# output3.net
KiCad netlist of a schematic drawn in Altium Designer
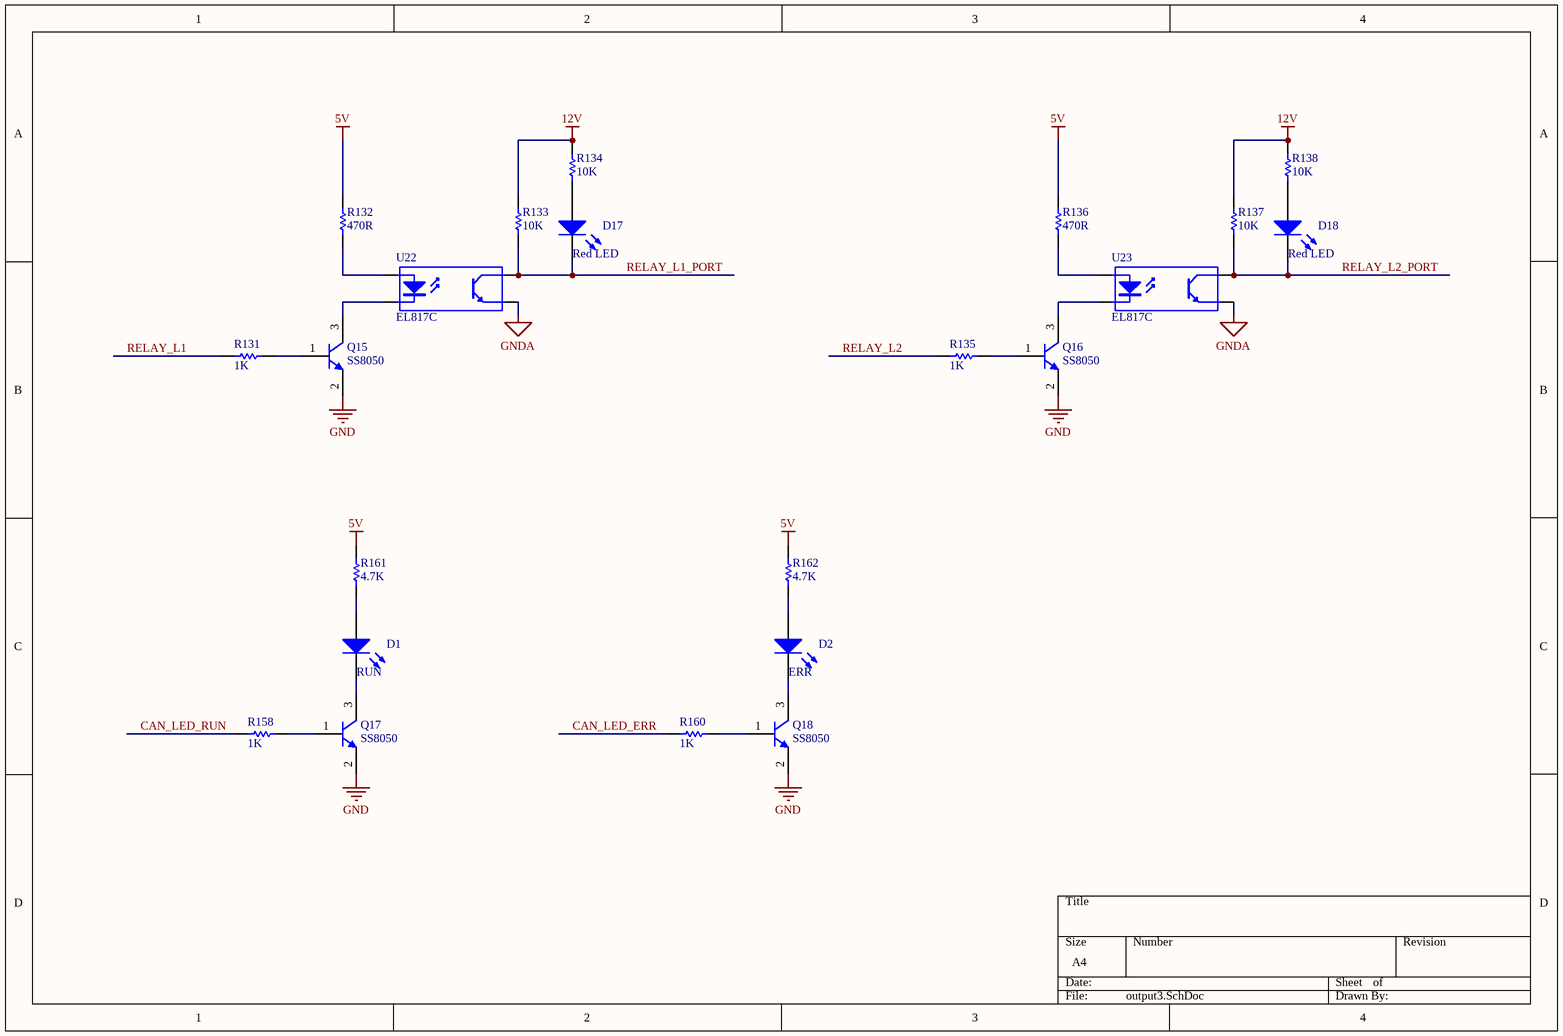
[diagram p0: output3.SchDoc]

(export (version "E")
  (design (tool "Eeschema 10.0.6"))
  (components
    (comp (ref "D1")
      (value "RUN")
      (footprint "CD2012-0805")
      (description "Green LED,Can bus indicator for run status.")
      (fields (field (name "PUBLISHER") "Altium Limited"))
      (libsource (lib "Miscellaneous Devices") (part "LED1"))
    )
    (comp (ref "D2")
      (value "ERR")
      (footprint "CD2012-0805")
      (description "Red LED,Can bus indicator for err status.")
      (fields (field (name "PUBLISHER") "Altium Limited"))
      (libsource (lib "Miscellaneous Devices") (part "LED1"))
    )
    (comp (ref "D17")
      (value "Red LED")
      (footprint "LED254A")
      (description "Red LED ,SIP, Dia =3mm")
      (fields (field (name "PUBLISHER") "Altium Limited"))
      (libsource (lib "Miscellaneous Devices") (part "LED1"))
    )
    (comp (ref "D18")
      (value "Red LED")
      (footprint "LED254A")
      (description "Red LED ,SIP, Dia =3mm")
      (fields (field (name "PUBLISHER") "Altium Limited"))
      (libsource (lib "Miscellaneous Devices") (part "LED1"))
    )
    (comp (ref "Q15")
      (value "SS8050")
      (footprint "SOT-23_N")
      (description "NPN BISS Transistor")
      (fields (field (name "PUBLISHER") "Altium Limited"))
      (libsource (lib "Philips Discrete BJT - Low Power") (part "PMMT491A"))
    )
    (comp (ref "Q16")
      (value "SS8050")
      (footprint "SOT-23_N")
      (description "NPN BISS Transistor")
      (fields (field (name "PUBLISHER") "Altium Limited"))
      (libsource (lib "Philips Discrete BJT - Low Power") (part "PMMT491A"))
    )
    (comp (ref "Q17")
      (value "SS8050")
      (footprint "SOT-23_N")
      (description "NPN BISS Transistor")
      (fields (field (name "PUBLISHER") "Altium Limited"))
      (libsource (lib "Philips Discrete BJT - Low Power") (part "PMMT491A"))
    )
    (comp (ref "Q18")
      (value "SS8050")
      (footprint "SOT-23_N")
      (description "NPN BISS Transistor")
      (fields (field (name "PUBLISHER") "Altium Limited"))
      (libsource (lib "Philips Discrete BJT - Low Power") (part "PMMT491A"))
    )
    (comp (ref "R131")
      (value "1K")
      (footprint "RESC2012M")
      (description "Resistor")
      (fields (field (name "PUBLISHER") "Altium Limited"))
      (libsource (lib "Miscellaneous Devices") (part "Res1"))
    )
    (comp (ref "R132")
      (value "470R")
      (footprint "RESC2012M")
      (description "Resistor")
      (fields (field (name "PUBLISHER") "Altium Limited"))
      (libsource (lib "Miscellaneous Devices") (part "Res1"))
    )
    (comp (ref "R133")
      (value "10K")
      (footprint "RESC2012M")
      (description "Resistor")
      (fields (field (name "PUBLISHER") "Altium Limited"))
      (libsource (lib "Miscellaneous Devices") (part "Res1"))
    )
    (comp (ref "R134")
      (value "10K")
      (footprint "RESC2012M")
      (description "Resistor")
      (fields (field (name "PUBLISHER") "Altium Limited"))
      (libsource (lib "Miscellaneous Devices") (part "Res1"))
    )
    (comp (ref "R135")
      (value "1K")
      (footprint "RESC2012M")
      (description "Resistor")
      (fields (field (name "PUBLISHER") "Altium Limited"))
      (libsource (lib "Miscellaneous Devices") (part "Res1"))
    )
    (comp (ref "R136")
      (value "470R")
      (footprint "RESC2012M")
      (description "Resistor")
      (fields (field (name "PUBLISHER") "Altium Limited"))
      (libsource (lib "Miscellaneous Devices") (part "Res1"))
    )
    (comp (ref "R137")
      (value "10K")
      (footprint "RESC2012M")
      (description "Resistor")
      (fields (field (name "PUBLISHER") "Altium Limited"))
      (libsource (lib "Miscellaneous Devices") (part "Res1"))
    )
    (comp (ref "R138")
      (value "10K")
      (footprint "RESC2012M")
      (description "Resistor")
      (fields (field (name "PUBLISHER") "Altium Limited"))
      (libsource (lib "Miscellaneous Devices") (part "Res1"))
    )
    (comp (ref "R158")
      (value "1K")
      (footprint "RESC2012M")
      (description "Resistor")
      (fields (field (name "PUBLISHER") "Altium Limited"))
      (libsource (lib "Miscellaneous Devices") (part "Res1"))
    )
    (comp (ref "R160")
      (value "1K")
      (footprint "RESC2012M")
      (description "Resistor")
      (fields (field (name "PUBLISHER") "Altium Limited"))
      (libsource (lib "Miscellaneous Devices") (part "Res1"))
    )
    (comp (ref "R161")
      (value "4.7K")
      (footprint "RESC2012M")
      (description "Resistor")
      (fields (field (name "PUBLISHER") "Altium Limited"))
      (libsource (lib "Miscellaneous Devices") (part "Res1"))
    )
    (comp (ref "R162")
      (value "4.7K")
      (footprint "RESC2012M")
      (description "Resistor")
      (fields (field (name "PUBLISHER") "Altium Limited"))
      (libsource (lib "Miscellaneous Devices") (part "Res1"))
    )
    (comp (ref "U22")
      (value "EL817C")
      (footprint "SO-4LA")
      (description "4-Pin Phototransistor Optocoupler")
      (fields (field (name "PUBLISHER") "Altium Limited"))
      (libsource (lib "Miscellaneous Devices") (part "Optoisolator1"))
    )
    (comp (ref "U23")
      (value "EL817C")
      (footprint "SO-4LA")
      (description "4-Pin Phototransistor Optocoupler")
      (fields (field (name "PUBLISHER") "Altium Limited"))
      (libsource (lib "Miscellaneous Devices") (part "Optoisolator1"))
    )
  )
  (nets
    (net (code "1") (name "/CAN_LED_ERR") (class "Default")
      (node (ref "R160") (pin "1") (pinfunction "1_1") (pintype "passive"))
    )
    (net (code "2") (name "/CAN_LED_RUN") (class "Default")
      (node (ref "R158") (pin "1") (pinfunction "1_1") (pintype "passive"))
    )
    (net (code "3") (name "/RELAY_L1") (class "Default")
      (node (ref "R131") (pin "1") (pinfunction "1_1") (pintype "passive"))
    )
    (net (code "4") (name "/RELAY_L1_PORT") (class "Default")
      (node (ref "D17") (pin "2") (pinfunction "K_2") (pintype "passive"))
      (node (ref "R133") (pin "1") (pinfunction "1_1") (pintype "passive"))
      (node (ref "U22") (pin "4") (pinfunction "C_4") (pintype "passive"))
    )
    (net (code "5") (name "/RELAY_L2") (class "Default")
      (node (ref "R135") (pin "1") (pinfunction "1_1") (pintype "passive"))
    )
    (net (code "6") (name "/RELAY_L2_PORT") (class "Default")
      (node (ref "D18") (pin "2") (pinfunction "K_2") (pintype "passive"))
      (node (ref "R137") (pin "1") (pinfunction "1_1") (pintype "passive"))
      (node (ref "U23") (pin "4") (pinfunction "C_4") (pintype "passive"))
    )
    (net (code "7") (name "5V") (class "Default")
      (node (ref "R132") (pin "1") (pinfunction "1_1") (pintype "passive"))
      (node (ref "R136") (pin "1") (pinfunction "1_1") (pintype "passive"))
      (node (ref "R161") (pin "1") (pinfunction "1_1") (pintype "passive"))
      (node (ref "R162") (pin "1") (pinfunction "1_1") (pintype "passive"))
    )
    (net (code "8") (name "12V") (class "Default")
      (node (ref "R133") (pin "2") (pinfunction "2_2") (pintype "passive"))
      (node (ref "R134") (pin "1") (pinfunction "1_1") (pintype "passive"))
      (node (ref "R137") (pin "2") (pinfunction "2_2") (pintype "passive"))
      (node (ref "R138") (pin "1") (pinfunction "1_1") (pintype "passive"))
    )
    (net (code "9") (name "GND") (class "Default")
      (node (ref "Q15") (pin "2") (pinfunction "E_2") (pintype "passive"))
      (node (ref "Q16") (pin "2") (pinfunction "E_2") (pintype "passive"))
      (node (ref "Q17") (pin "2") (pinfunction "E_2") (pintype "passive"))
      (node (ref "Q18") (pin "2") (pinfunction "E_2") (pintype "passive"))
    )
    (net (code "10") (name "GNDA") (class "Default")
      (node (ref "U22") (pin "3") (pinfunction "E_3") (pintype "passive"))
      (node (ref "U23") (pin "3") (pinfunction "E_3") (pintype "passive"))
    )
    (net (code "11") (name "Net-(D1-A)") (class "Default")
      (node (ref "D1") (pin "1") (pinfunction "A_1") (pintype "passive"))
      (node (ref "R161") (pin "2") (pinfunction "2_2") (pintype "passive"))
    )
    (net (code "12") (name "Net-(D1-K)") (class "Default")
      (node (ref "D1") (pin "2") (pinfunction "K_2") (pintype "passive"))
      (node (ref "Q17") (pin "3") (pinfunction "C_3") (pintype "passive"))
    )
    (net (code "13") (name "Net-(D2-A)") (class "Default")
      (node (ref "D2") (pin "1") (pinfunction "A_1") (pintype "passive"))
      (node (ref "R162") (pin "2") (pinfunction "2_2") (pintype "passive"))
    )
    (net (code "14") (name "Net-(D2-K)") (class "Default")
      (node (ref "D2") (pin "2") (pinfunction "K_2") (pintype "passive"))
      (node (ref "Q18") (pin "3") (pinfunction "C_3") (pintype "passive"))
    )
    (net (code "15") (name "Net-(D17-A)") (class "Default")
      (node (ref "D17") (pin "1") (pinfunction "A_1") (pintype "passive"))
      (node (ref "R134") (pin "2") (pinfunction "2_2") (pintype "passive"))
    )
    (net (code "16") (name "Net-(D18-A)") (class "Default")
      (node (ref "D18") (pin "1") (pinfunction "A_1") (pintype "passive"))
      (node (ref "R138") (pin "2") (pinfunction "2_2") (pintype "passive"))
    )
    (net (code "17") (name "Net-(Q15-B)") (class "Default")
      (node (ref "Q15") (pin "1") (pinfunction "B_1") (pintype "passive"))
      (node (ref "R131") (pin "2") (pinfunction "2_2") (pintype "passive"))
    )
    (net (code "18") (name "Net-(Q15-C)") (class "Default")
      (node (ref "Q15") (pin "3") (pinfunction "C_3") (pintype "passive"))
      (node (ref "U22") (pin "2") (pinfunction "K_2") (pintype "passive"))
    )
    (net (code "19") (name "Net-(Q16-B)") (class "Default")
      (node (ref "Q16") (pin "1") (pinfunction "B_1") (pintype "passive"))
      (node (ref "R135") (pin "2") (pinfunction "2_2") (pintype "passive"))
    )
    (net (code "20") (name "Net-(Q16-C)") (class "Default")
      (node (ref "Q16") (pin "3") (pinfunction "C_3") (pintype "passive"))
      (node (ref "U23") (pin "2") (pinfunction "K_2") (pintype "passive"))
    )
    (net (code "21") (name "Net-(Q17-B)") (class "Default")
      (node (ref "Q17") (pin "1") (pinfunction "B_1") (pintype "passive"))
      (node (ref "R158") (pin "2") (pinfunction "2_2") (pintype "passive"))
    )
    (net (code "22") (name "Net-(Q18-B)") (class "Default")
      (node (ref "Q18") (pin "1") (pinfunction "B_1") (pintype "passive"))
      (node (ref "R160") (pin "2") (pinfunction "2_2") (pintype "passive"))
    )
    (net (code "23") (name "Net-(U22-A)") (class "Default")
      (node (ref "R132") (pin "2") (pinfunction "2_2") (pintype "passive"))
      (node (ref "U22") (pin "1") (pinfunction "A_1") (pintype "passive"))
    )
    (net (code "24") (name "Net-(U23-A)") (class "Default")
      (node (ref "R136") (pin "2") (pinfunction "2_2") (pintype "passive"))
      (node (ref "U23") (pin "1") (pinfunction "A_1") (pintype "passive"))
    )
  )
)
